# Connectors.net
KiCad netlist of a schematic drawn in Altium Designer
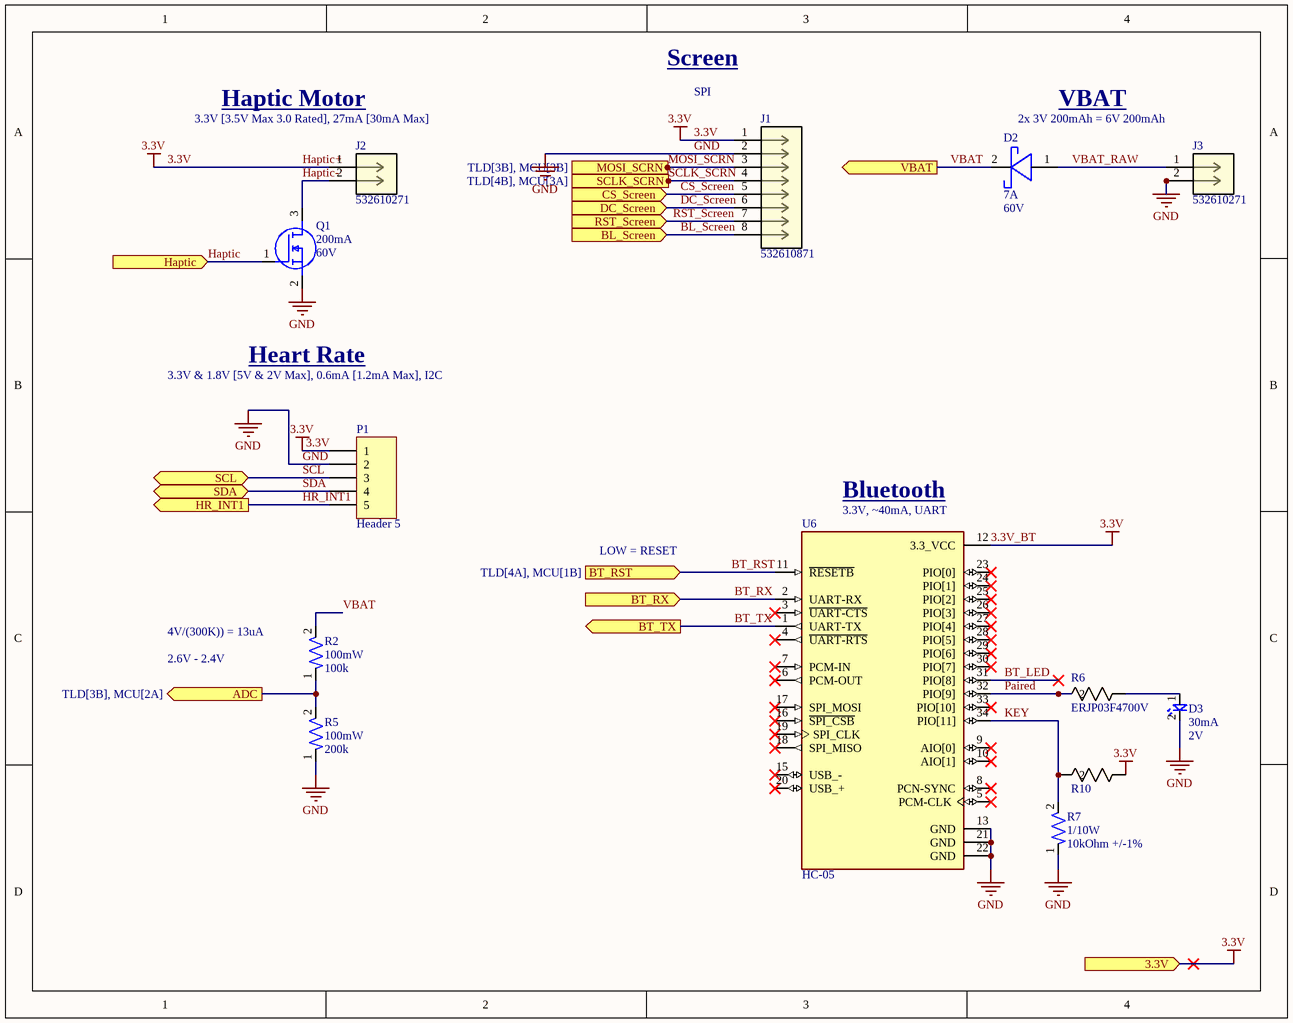
[diagram p0: Connectors.SchDoc]

(export (version "E")
  (design (tool "Eeschema 10.0.6"))
  (components
    (comp (ref "D2")
      (value "PDS760-13")
      (footprint "DO-POWERDI5")
      (description "DIODE SCHOTTKY 60V 7A POWERDI5")
      (fields (field (name "FORWARD CURRENT") "7A") (field (name "REVERSE VOLTAGE (DC)") "60V"))
      (libsource (lib "JLC_25") (part "DIO-SCHOTTKY-0001"))
    )
    (comp (ref "D3")
      (value "BL-HKC36G-AV-TRB")
      (footprint "LED-0603")
      (description "LED YELLOW CLEAR 0603 SMD")
      (fields (field (name "FORWARD CURRENT") "30mA") (field (name "FORWARD VOLTAGE") "2V"))
      (libsource (lib "JLC_25") (part "LED-0001"))
    )
    (comp (ref "J1")
      (value "532610871")
      (footprint "CONN_532610001-SD_08_MOL")
      (description "No Description Available")
      (libsource (lib "eecs373Lib") (part "Header-PICO-8"))
    )
    (comp (ref "J2")
      (value "532610271")
      (footprint "CONN_532610001-SD_02_MOL")
      (description "No Description Available")
      (libsource (lib "eecs373Lib") (part "Header-PICO-2"))
    )
    (comp (ref "J3")
      (value "532610271")
      (footprint "CONN_532610001-SD_02_MOL")
      (description "No Description Available")
      (libsource (lib "eecs373Lib") (part "Header-PICO-2"))
    )
    (comp (ref "P1")
      (value "Header 5")
      (footprint "HDR1X5")
      (description "Header, 5-Pin")
      (fields (field (name "PUBLISHER") "Altium Limited"))
      (libsource (lib "Miscellaneous Connectors") (part "Header 5"))
    )
    (comp (ref "Q1")
      (value "T2N7002AK,LM")
      (footprint "IC-SOT23-3")
      (description "MOSFET N-CH 60V 200MA SOT23")
      (fields (field (name "CONTINUOUS CURRENT") "200mA") (field (name "VOLTAGE") "60V"))
      (libsource (lib "JLC_25") (part "NMOS-200MA-0001"))
    )
    (comp (ref "R2")
      (value "RC0603FR-07100KL")
      (footprint "RES-0603")
      (description "RES SMD 100K OHM 1% 1/10W 0603")
      (fields
        (field (name "TOLERANCE") "1%")
        (field (name "POWER") "100mW")
        (field (name "RESISTANCE") "100k")
      )
      (libsource (lib "JLC_25") (part "RES-100k-0001"))
    )
    (comp (ref "R5")
      (value "RC0603FR-07200KL")
      (footprint "RES-0603")
      (description "RES SMD 200K OHM 1% 1/10W 0603")
      (fields
        (field (name "TOLERANCE") "1%")
        (field (name "POWER") "100mW")
        (field (name "RESISTANCE") "200k")
      )
      (libsource (lib "JLC_25") (part "RES-200k-0001"))
    )
    (comp (ref "R6")
      (value "ERJP03F4700V")
      (footprint "RES_ERJP03_PAN")
      (libsource (lib "eecs373Lib") (part "RES-470-0603"))
    )
    (comp (ref "R7")
      (value "RC0603FR-0710KP")
      (footprint "RES-0603")
      (description "RES SMD 10K OHM 1% 1/10W 0603")
      (fields
        (field (name "MANUFACTURER") "YAGEO")
        (field (name "POWER RATING") "1/10W")
        (field (name "RESISTANCE") "10kOhm +/-1%")
      )
      (libsource (lib "MasterLib") (part "RES-10K-0002"))
    )
    (comp (ref "R10")
      (value "CRCW12100000Z0EA")
      (footprint "RES_CRCW_1210_VIS")
      (description "No Description Available")
      (libsource (lib "eecs373Lib") (part "RES-0-1"))
    )
    (comp (ref "U6")
      (value "HC-05")
      (footprint "XCVR_HC-05")
      (description "Bluetooth to Serial Port Module")
      (fields (field (name "MF") "ITead Studio"))
      (libsource (lib "eecs373Lib") (part "HC-05"))
    )
  )
  (nets
    (net (code "1") (name "/ADC") (class "Default")
      (node (ref "R2") (pin "1") (pinfunction "1_1") (pintype "passive"))
      (node (ref "R5") (pin "2") (pinfunction "2_2") (pintype "passive"))
    )
    (net (code "2") (name "/BL_Screen") (class "Default")
      (node (ref "J1") (pin "8") (pinfunction "8_8") (pintype "passive"))
    )
    (net (code "3") (name "/BT_LED") (class "Default")
      (node (ref "U6") (pin "31") (pinfunction "PIO[8]_31") (pintype "bidirectional+no_connect"))
    )
    (net (code "4") (name "/BT_RST") (class "Default")
      (node (ref "U6") (pin "11") (pinfunction "~{RESETB}_11") (pintype "input"))
    )
    (net (code "5") (name "/BT_RX") (class "Default")
      (node (ref "U6") (pin "2") (pinfunction "UART-RX_2") (pintype "input"))
    )
    (net (code "6") (name "/BT_TX") (class "Default")
      (node (ref "U6") (pin "1") (pinfunction "UART-TX_1") (pintype "output"))
    )
    (net (code "7") (name "/CS_Screen") (class "Default")
      (node (ref "J1") (pin "5") (pinfunction "5_5") (pintype "passive"))
    )
    (net (code "8") (name "/DC_Screen") (class "Default")
      (node (ref "J1") (pin "6") (pinfunction "6_6") (pintype "passive"))
    )
    (net (code "9") (name "/HR_INT1") (class "Default")
      (node (ref "P1") (pin "5") (pinfunction "5_5") (pintype "passive"))
    )
    (net (code "10") (name "/Haptic") (class "Default")
      (node (ref "Q1") (pin "1") (pinfunction "G_1") (pintype "passive"))
    )
    (net (code "11") (name "/Haptic-") (class "Default")
      (node (ref "J2") (pin "2") (pinfunction "2_2") (pintype "passive"))
      (node (ref "Q1") (pin "3") (pinfunction "D_3") (pintype "passive"))
    )
    (net (code "12") (name "/KEY") (class "Default")
      (node (ref "R10") (pin "2") (pinfunction "2_2") (pintype "passive"))
      (node (ref "R7") (pin "2") (pinfunction "2_2") (pintype "passive"))
      (node (ref "U6") (pin "34") (pinfunction "PIO[11]_34") (pintype "bidirectional"))
    )
    (net (code "13") (name "/MOSI_SCRN") (class "Default")
      (node (ref "J1") (pin "3") (pinfunction "3_3") (pintype "passive"))
    )
    (net (code "14") (name "/Paired") (class "Default")
      (node (ref "R6") (pin "2") (pinfunction "2_2") (pintype "passive"))
      (node (ref "U6") (pin "32") (pinfunction "PIO[9]_32") (pintype "bidirectional"))
    )
    (net (code "15") (name "/RST_Screen") (class "Default")
      (node (ref "J1") (pin "7") (pinfunction "7_7") (pintype "passive"))
    )
    (net (code "16") (name "/SCL") (class "Default")
      (node (ref "P1") (pin "3") (pinfunction "3_3") (pintype "passive"))
    )
    (net (code "17") (name "/SCLK_SCRN") (class "Default")
      (node (ref "J1") (pin "4") (pinfunction "4_4") (pintype "passive"))
    )
    (net (code "18") (name "/SDA") (class "Default")
      (node (ref "P1") (pin "4") (pinfunction "4_4") (pintype "passive"))
    )
    (net (code "19") (name "/VBAT") (class "Default")
      (node (ref "D2") (pin "2") (pinfunction "ANODE_2") (pintype "passive"))
      (node (ref "R2") (pin "2") (pinfunction "2_2") (pintype "passive"))
    )
    (net (code "20") (name "/VBAT_RAW") (class "Default")
      (node (ref "D2") (pin "1") (pinfunction "CATHODE_1") (pintype "passive"))
      (node (ref "J3") (pin "1") (pinfunction "1_1") (pintype "passive"))
    )
    (net (code "21") (name "3.3V") (class "Default")
      (node (ref "J1") (pin "1") (pinfunction "1_1") (pintype "passive"))
      (node (ref "J2") (pin "1") (pinfunction "1_1") (pintype "passive"))
      (node (ref "P1") (pin "1") (pinfunction "1_1") (pintype "passive"))
      (node (ref "R10") (pin "1") (pinfunction "1_1") (pintype "passive"))
      (node (ref "U6") (pin "12") (pinfunction "3.3_VCC_12") (pintype "power_in"))
    )
    (net (code "22") (name "GND") (class "Default")
      (node (ref "D3") (pin "2") (pinfunction "2_2") (pintype "passive"))
      (node (ref "J1") (pin "2") (pinfunction "2_2") (pintype "passive"))
      (node (ref "J3") (pin "2") (pinfunction "2_2") (pintype "passive"))
      (node (ref "P1") (pin "2") (pinfunction "2_2") (pintype "passive"))
      (node (ref "Q1") (pin "2") (pinfunction "S_2") (pintype "passive"))
      (node (ref "R5") (pin "1") (pinfunction "1_1") (pintype "passive"))
      (node (ref "R7") (pin "1") (pinfunction "1_1") (pintype "passive"))
      (node (ref "U6") (pin "13") (pinfunction "GND_13") (pintype "power_in"))
      (node (ref "U6") (pin "21") (pinfunction "GND_21") (pintype "power_in"))
      (node (ref "U6") (pin "22") (pinfunction "GND_22") (pintype "power_in"))
    )
    (net (code "23") (name "Net-(D3-Pad1)") (class "Default")
      (node (ref "D3") (pin "1") (pinfunction "1_1") (pintype "passive"))
      (node (ref "R6") (pin "1") (pinfunction "1_1") (pintype "passive"))
    )
    (net (code "24") (name "unconnected-(U6-AIO[0]-Pad9)") (class "Default")
      (node (ref "U6") (pin "9") (pinfunction "AIO[0]_9") (pintype "bidirectional+no_connect"))
    )
    (net (code "25") (name "unconnected-(U6-AIO[1]-Pad10)") (class "Default")
      (node (ref "U6") (pin "10") (pinfunction "AIO[1]_10") (pintype "bidirectional+no_connect"))
    )
    (net (code "26") (name "unconnected-(U6-PCM-CLK-Pad5)") (class "Default")
      (node (ref "U6") (pin "5") (pinfunction "PCM-CLK_5") (pintype "bidirectional+no_connect"))
    )
    (net (code "27") (name "unconnected-(U6-PCM-IN-Pad7)") (class "Default")
      (node (ref "U6") (pin "7") (pinfunction "PCM-IN_7") (pintype "input+no_connect"))
    )
    (net (code "28") (name "unconnected-(U6-PCM-OUT-Pad6)") (class "Default")
      (node (ref "U6") (pin "6") (pinfunction "PCM-OUT_6") (pintype "output+no_connect"))
    )
    (net (code "29") (name "unconnected-(U6-PCN-SYNC-Pad8)") (class "Default")
      (node (ref "U6") (pin "8") (pinfunction "PCN-SYNC_8") (pintype "bidirectional+no_connect"))
    )
    (net (code "30") (name "unconnected-(U6-PIO[0]-Pad23)") (class "Default")
      (node (ref "U6") (pin "23") (pinfunction "PIO[0]_23") (pintype "bidirectional+no_connect"))
    )
    (net (code "31") (name "unconnected-(U6-PIO[1]-Pad24)") (class "Default")
      (node (ref "U6") (pin "24") (pinfunction "PIO[1]_24") (pintype "bidirectional+no_connect"))
    )
    (net (code "32") (name "unconnected-(U6-PIO[2]-Pad25)") (class "Default")
      (node (ref "U6") (pin "25") (pinfunction "PIO[2]_25") (pintype "bidirectional+no_connect"))
    )
    (net (code "33") (name "unconnected-(U6-PIO[3]-Pad26)") (class "Default")
      (node (ref "U6") (pin "26") (pinfunction "PIO[3]_26") (pintype "bidirectional+no_connect"))
    )
    (net (code "34") (name "unconnected-(U6-PIO[4]-Pad27)") (class "Default")
      (node (ref "U6") (pin "27") (pinfunction "PIO[4]_27") (pintype "bidirectional+no_connect"))
    )
    (net (code "35") (name "unconnected-(U6-PIO[5]-Pad28)") (class "Default")
      (node (ref "U6") (pin "28") (pinfunction "PIO[5]_28") (pintype "bidirectional+no_connect"))
    )
    (net (code "36") (name "unconnected-(U6-PIO[6]-Pad29)") (class "Default")
      (node (ref "U6") (pin "29") (pinfunction "PIO[6]_29") (pintype "bidirectional+no_connect"))
    )
    (net (code "37") (name "unconnected-(U6-PIO[7]-Pad30)") (class "Default")
      (node (ref "U6") (pin "30") (pinfunction "PIO[7]_30") (pintype "bidirectional+no_connect"))
    )
    (net (code "38") (name "unconnected-(U6-PIO[10]-Pad33)") (class "Default")
      (node (ref "U6") (pin "33") (pinfunction "PIO[10]_33") (pintype "bidirectional+no_connect"))
    )
    (net (code "39") (name "unconnected-(U6-SPI_CLK-Pad19)") (class "Default")
      (node (ref "U6") (pin "19") (pinfunction "SPI_CLK_19") (pintype "input+no_connect"))
    )
    (net (code "40") (name "unconnected-(U6-SPI_MISO-Pad18)") (class "Default")
      (node (ref "U6") (pin "18") (pinfunction "SPI_MISO_18") (pintype "output+no_connect"))
    )
    (net (code "41") (name "unconnected-(U6-SPI_MOSI-Pad17)") (class "Default")
      (node (ref "U6") (pin "17") (pinfunction "SPI_MOSI_17") (pintype "input+no_connect"))
    )
    (net (code "42") (name "unconnected-(U6-USB_+-Pad20)") (class "Default")
      (node (ref "U6") (pin "20") (pinfunction "USB_+_20") (pintype "bidirectional+no_connect"))
    )
    (net (code "43") (name "unconnected-(U6-USB_--Pad15)") (class "Default")
      (node (ref "U6") (pin "15") (pinfunction "USB_-_15") (pintype "bidirectional+no_connect"))
    )
    (net (code "44") (name "unconnected-(U6-~{SPI_CSB}-Pad16)") (class "Default")
      (node (ref "U6") (pin "16") (pinfunction "~{SPI_CSB}_16") (pintype "input+no_connect"))
    )
    (net (code "45") (name "unconnected-(U6-~{UART-CTS}-Pad3)") (class "Default")
      (node (ref "U6") (pin "3") (pinfunction "~{UART-CTS}_3") (pintype "input+no_connect"))
    )
    (net (code "46") (name "unconnected-(U6-~{UART-RTS}-Pad4)") (class "Default")
      (node (ref "U6") (pin "4") (pinfunction "~{UART-RTS}_4") (pintype "output+no_connect"))
    )
  )
)
